# CameraCageBB.net
KiCad netlist of a schematic drawn in Altium Designer
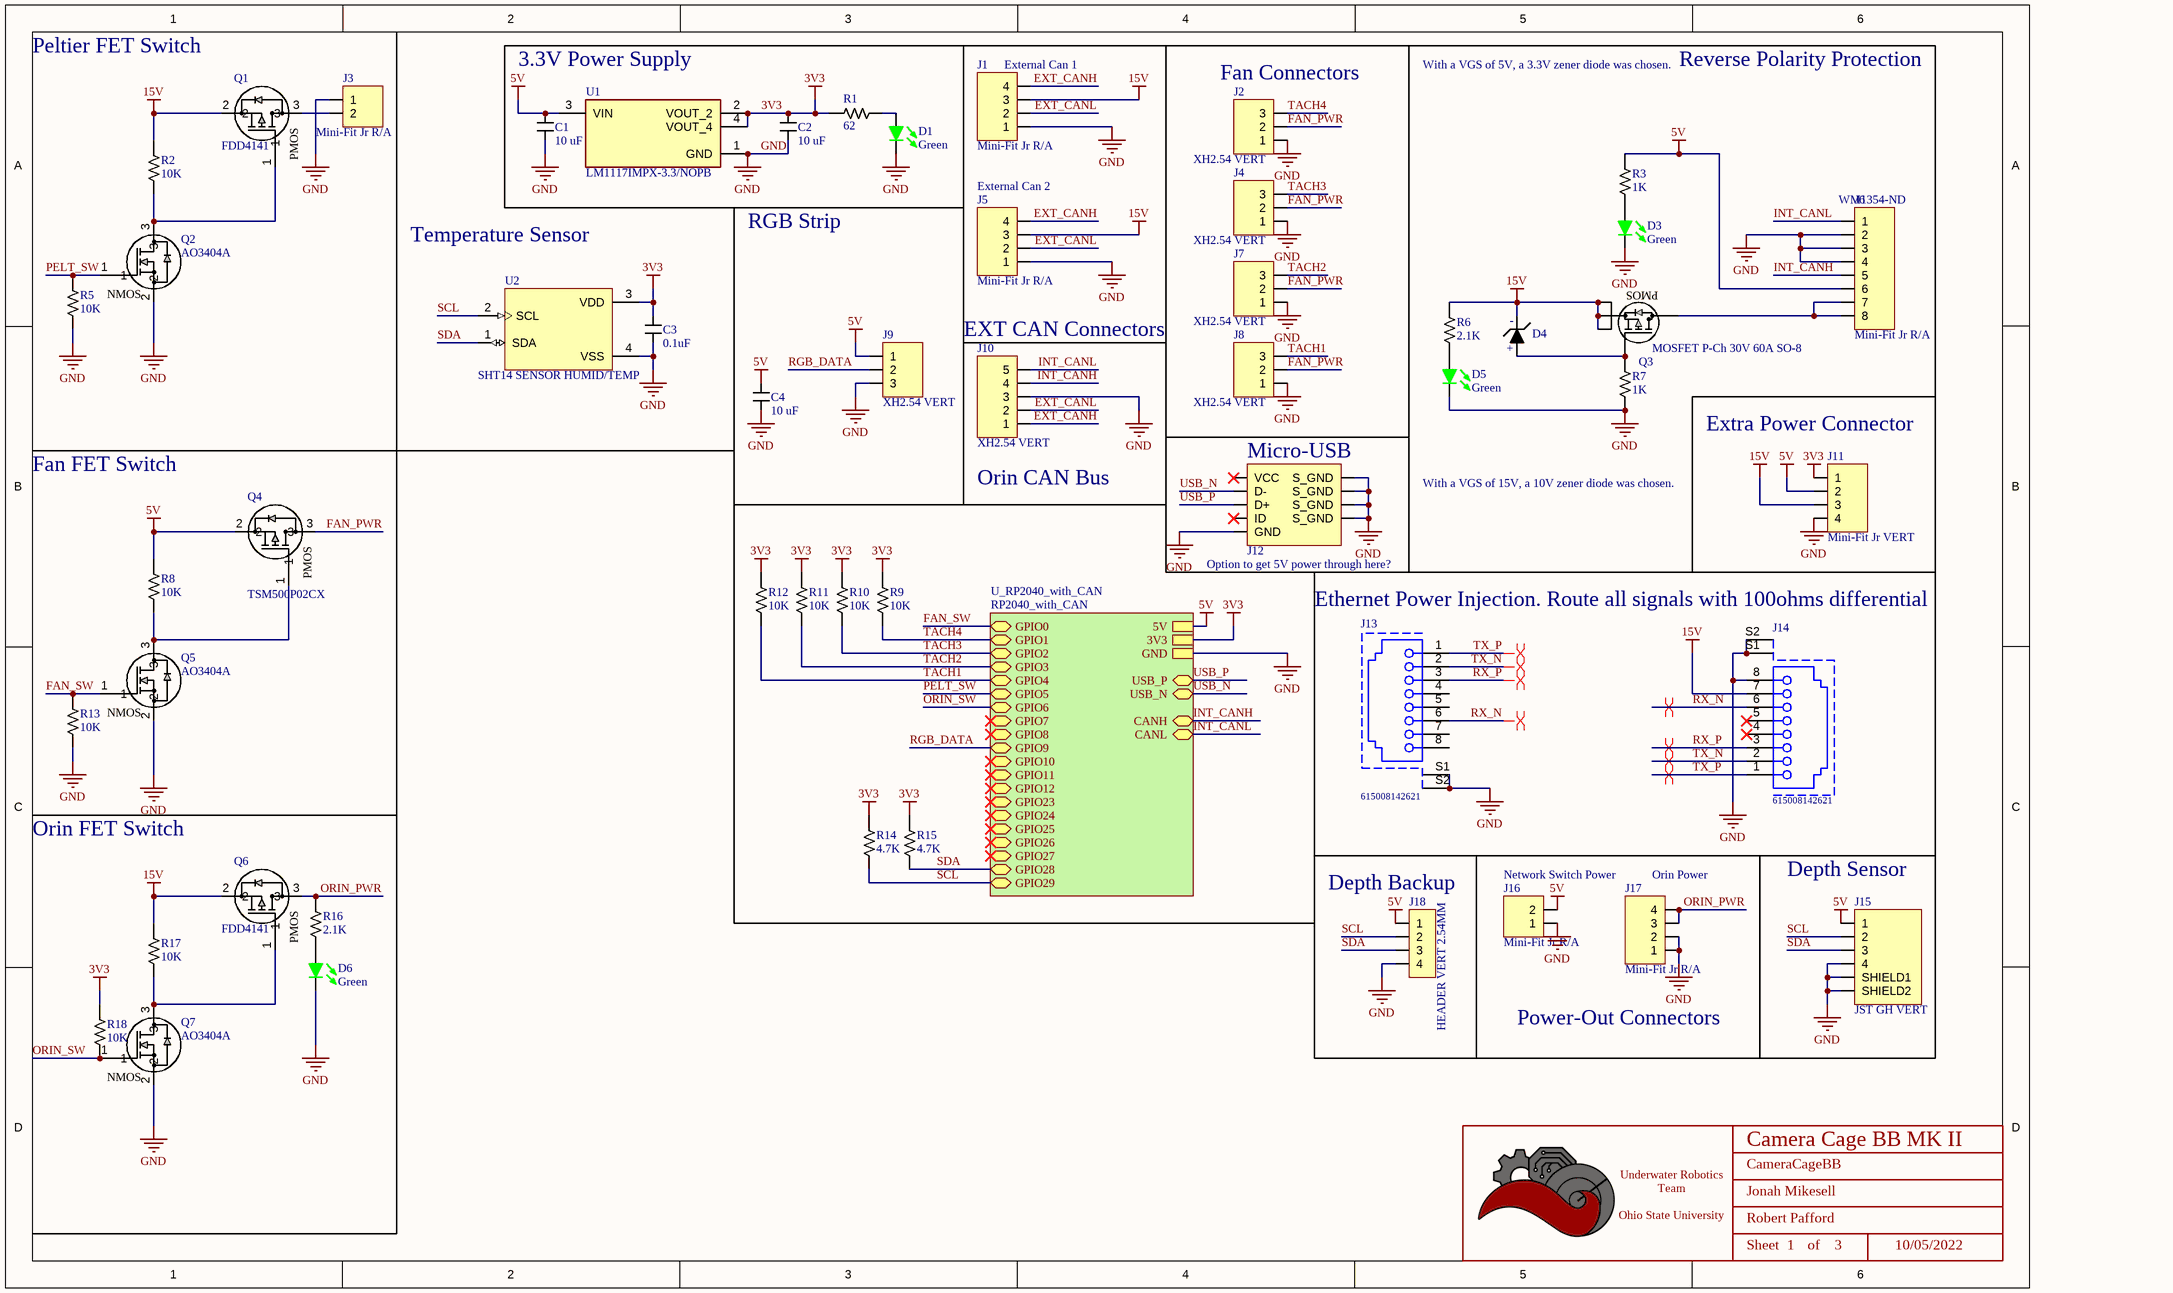
[diagram p0: CameraCageBB.SchDoc]

(export (version "E")
  (design (tool "Eeschema 10.0.6"))
  (components
    (comp (ref "*")
      (value "Title_Block")
      (footprint "LOGO")
      (description "UWRT Schematic Title Block Template\r\n\r\nCreated June 2021, Dylan Trainor")
      (libsource (lib "UWRT") (part "Title_Block"))
    )
    (comp (ref "C1")
      (value "10uF Ceramic 6.3V")
      (footprint "CAPACITOR_0603")
      (description "Cap 10uF 6.3V +/-20%\r\nCeramic 0603")
      (fields
        (field (name "TOLERANCE") "+/- 20%")
        (field (name "VOLTAGE") "6.3V")
        (field (name "VALUE (UF)") "10 uF")
        (field (name "MADE BY") "Flip B")
      )
      (libsource (lib "Capacitors") (part "CAPACITOR_10uF_0603"))
    )
    (comp (ref "C2")
      (value "10uF Ceramic 6.3V")
      (footprint "CAPACITOR_0603")
      (description "Cap 10uF 6.3V +/-20%\r\nCeramic 0603")
      (fields
        (field (name "TOLERANCE") "+/- 20%")
        (field (name "VOLTAGE") "6.3V")
        (field (name "VALUE (UF)") "10 uF")
        (field (name "MADE BY") "Flip B")
      )
      (libsource (lib "Capacitors") (part "CAPACITOR_10uF_0603"))
    )
    (comp (ref "C3")
      (value "0.1uF")
      (footprint "CAPACITOR_0603")
      (description "Cap 100nF 6.3V +/-10%\r\nCeramic 0603")
      (fields
        (field (name "TOLERANCE") "+/- 10%")
        (field (name "VOLTAGE") "6.3V")
        (field (name "MADE BY") "Flip B")
      )
      (libsource (lib "Capacitors") (part "CAPACITOR_0.1uF_0603"))
    )
    (comp (ref "C4")
      (value "10uF Ceramic 6.3V")
      (footprint "CAPACITOR_0603")
      (description "Cap 10uF 6.3V +/-20%\r\nCeramic 0603")
      (fields
        (field (name "TOLERANCE") "+/- 20%")
        (field (name "VOLTAGE") "6.3V")
        (field (name "VALUE (UF)") "10 uF")
        (field (name "MADE BY") "Flip B")
      )
      (libsource (lib "Capacitors") (part "CAPACITOR_10uF_0603"))
    )
    (comp (ref "D1")
      (value "IN-S63AT5G")
      (footprint "LED_0603")
      (description "LED Green Vf= 3V If = 0.005A\r\nIN-S63AT5G")
      (fields (field (name "COLOR") "Green") (field (name "MADE BY") "Robert Pafford"))
      (libsource (lib "Diodes") (part "LED_Green_0603_3V"))
    )
    (comp (ref "D3")
      (value "IN-S63AT5G")
      (footprint "LED_0603")
      (description "LED Green Vf= 3V If = 0.005A\r\nIN-S63AT5G")
      (fields (field (name "COLOR") "Green") (field (name "MADE BY") "Robert Pafford"))
      (libsource (lib "Diodes") (part "LED_Green_0603_3V"))
    )
    (comp (ref "D4")
      (value "Zener_Diode_10V_410mW")
      (footprint "SOD-123")
      (description "Zener Diode ¦ 10 V ¦ 410 mW ¦ SOD 123")
      (fields (field (name "POWER") "410mW") (field (name "MADE BY") "Nathan A"))
      (libsource (lib "Diodes") (part "Zener_Diode_10V_410mW"))
    )
    (comp (ref "D5")
      (value "IN-S63AT5G")
      (footprint "LED_0603")
      (description "LED Green Vf= 3V If = 0.005A\r\nIN-S63AT5G")
      (fields (field (name "COLOR") "Green") (field (name "MADE BY") "Robert Pafford"))
      (libsource (lib "Diodes") (part "LED_Green_0603_3V"))
    )
    (comp (ref "D6")
      (value "IN-S63AT5G")
      (footprint "LED_0603")
      (description "LED Green Vf= 3V If = 0.005A\r\nIN-S63AT5G")
      (fields (field (name "COLOR") "Green") (field (name "MADE BY") "Robert Pafford"))
      (libsource (lib "Diodes") (part "LED_Green_0603_3V"))
    )
    (comp (ref "J1")
      (value "Mini-Fit Jr R/A")
      (footprint "CONN_MOLEX_MINIFIT JR_4 POS_R/A")
      (description "Molex Minifit Jr. 5569 \r\n4 Pos R/A Natural")
      (fields (field (name "MANUFACTURER") "Molex") (field (name "CREATED BY") "Flip B"))
      (libsource (lib "Connectors") (part "CONN_MOLEX_MINIFIT JR_4POS_R/A"))
    )
    (comp (ref "J2")
      (value "XH2.54 VERT")
      (footprint "CONN_JST_XH254_3POS_VERT")
      (description "JST XH 2.54mm Pitch 3 Pos Vertical")
      (fields (field (name "MANUFACTURER") "JST") (field (name "CREATED BY") "Robert P"))
      (libsource (lib "") (part "CONN_JST_XH254_3POS_VERT_1"))
    )
    (comp (ref "J3")
      (value "Mini-Fit Jr R/A")
      (footprint "CONN_MOLEX_MINIFIT JR_2 POS_R/A")
      (description "Molex Minifit Jr. 5569 \r\n2 Pos R/A Natural")
      (fields (field (name "MANUFACTURER") "Molex") (field (name "CREATED BY") "Robert P"))
      (libsource (lib "") (part "CONN_MOLEX_MINIFIT JR_2POS_R/A_1"))
    )
    (comp (ref "J4")
      (value "XH2.54 VERT")
      (footprint "CONN_JST_XH254_3POS_VERT")
      (description "JST XH 2.54mm Pitch 3 Pos Vertical")
      (fields (field (name "MANUFACTURER") "JST") (field (name "CREATED BY") "Robert P"))
      (libsource (lib "") (part "CONN_JST_XH254_3POS_VERT_1"))
    )
    (comp (ref "J5")
      (value "Mini-Fit Jr R/A")
      (footprint "CONN_MOLEX_MINIFIT JR_4 POS_R/A")
      (description "Molex Minifit Jr. 5569 \r\n4 Pos R/A Natural")
      (fields (field (name "MANUFACTURER") "Molex") (field (name "CREATED BY") "Flip B"))
      (libsource (lib "Connectors") (part "CONN_MOLEX_MINIFIT JR_4POS_R/A"))
    )
    (comp (ref "J6")
      (value "Mini-Fit Jr R/A")
      (footprint "CONN_MOLEX_MINIFIT JR_8 POS_R/A")
      (description "Molex Minifit Jr. 5569 \r\n8 Pos R/A Natural")
      (fields
        (field (name "MANUFACTURER") "Molex")
        (field (name "SUPPLIER PART NUMBER 1") "WM1354-ND")
        (field (name "CREATED BY") "Flip B")
      )
      (libsource (lib "Connectors") (part "CONN_MOLEX_MINIFIT JR_8POS_R/A"))
    )
    (comp (ref "J7")
      (value "XH2.54 VERT")
      (footprint "CONN_JST_XH254_3POS_VERT")
      (description "JST XH 2.54mm Pitch 3 Pos Vertical")
      (fields (field (name "MANUFACTURER") "JST") (field (name "CREATED BY") "Robert P"))
      (libsource (lib "") (part "CONN_JST_XH254_3POS_VERT_1"))
    )
    (comp (ref "J8")
      (value "XH2.54 VERT")
      (footprint "CONN_JST_XH254_3POS_VERT")
      (description "JST XH 2.54mm Pitch 3 Pos Vertical")
      (fields (field (name "MANUFACTURER") "JST") (field (name "CREATED BY") "Robert P"))
      (libsource (lib "") (part "CONN_JST_XH254_3POS_VERT_1"))
    )
    (comp (ref "J9")
      (value "XH2.54 VERT")
      (footprint "CONN_JST_XH254_3POS_VERT")
      (description "JST XH 2.54mm Pitch 3 Pos Vertical")
      (fields (field (name "MANUFACTURER") "JST") (field (name "CREATED BY") "Robert P"))
      (libsource (lib "Connectors") (part "CONN_JST_XH254_3POS_VERT"))
    )
    (comp (ref "J10")
      (value "XH2.54 VERT")
      (footprint "CONN_JST_XH254_5POS_VERT")
      (description "JST XH 2.54mm Pitch 5 Pos Vertical")
      (fields (field (name "MANUFACTURER") "JST") (field (name "CREATED BY") "Robert P"))
      (libsource (lib "Connectors") (part "CONN_JST_XH254_5POS_VERT"))
    )
    (comp (ref "J11")
      (value "Mini-Fit Jr VERT")
      (footprint "CONN_MOLEX_MINIFIT JR_4 POS_VERT")
      (description "Molex Minifit Jr. 5566 \r\n4 Pos Vertical Natural")
      (fields (field (name "MANUFACTURER") "Molex") (field (name "CREATED BY") "Robert P"))
      (libsource (lib "Connectors") (part "CONN_MOLEX_MINIFIT JR_4POS_VERT"))
    )
    (comp (ref "J12")
      (value "USB_MICRO R/A")
      (footprint "CONN_MINIUSB")
      (description "Amphenol Micro USB-B\r\nUSB2.0 5 Pin Right Angle SMD")
      (fields (field (name "MANUFACTURER") "Amphenol") (field (name "CREATED BY") "Flip B"))
      (libsource (lib "Connectors") (part "CONN_MICROUSB"))
    )
    (comp (ref "J13")
      (value "615008142621")
      (footprint "615008142621")
      (fields (field (name "MANUFACTURER") "Wurth Elektronik") (field (name "PUBLISHER") "WurthElektronik"))
      (libsource (lib "Altium Content Vault") (part "WE-CN-1P-2F-J8"))
    )
    (comp (ref "J14")
      (value "615008142621")
      (footprint "615008142621")
      (fields (field (name "MANUFACTURER") "Wurth Elektronik") (field (name "PUBLISHER") "WurthElektronik"))
      (libsource (lib "Altium Content Vault") (part "WE-CN-1P-2F-J8"))
    )
    (comp (ref "J15")
      (value "JST GH VERT")
      (footprint "CONN_JST_BM04B-GHS-TBT(LF)(SN)(N)")
      (description "JST GH Pitch 4 Pos Vertical")
      (fields (field (name "MANUFACTURER") "JST") (field (name "CREATED BY") "Robert P"))
      (libsource (lib "Connectors") (part "CONN_JST_GH_4POS_VERT"))
    )
    (comp (ref "J16")
      (value "Mini-Fit Jr R/A")
      (footprint "CONN_MOLEX_MINIFIT JR_2 POS_R/A")
      (description "Molex Minifit Jr. 5569 \r\n2 Pos R/A Natural")
      (fields (field (name "MANUFACTURER") "Molex") (field (name "CREATED BY") "Robert P"))
      (libsource (lib "Connectors") (part "CONN_MOLEX_MINIFIT JR_2POS_R/A"))
    )
    (comp (ref "J17")
      (value "Mini-Fit Jr R/A")
      (footprint "CONN_MOLEX_MINIFIT JR_4 POS_R/A")
      (description "Molex Minifit Jr. 5569 \r\n4 Pos R/A Natural")
      (fields (field (name "MANUFACTURER") "Molex") (field (name "CREATED BY") "Flip B"))
      (libsource (lib "Connectors") (part "CONN_MOLEX_MINIFIT JR_4POS_R/A"))
    )
    (comp (ref "J18")
      (value "HEADER VERT 2.54MM")
      (footprint "HEADER_4PIN_2.54MM")
      (description "CONN HEADER VERT 4POS 2.54MM")
      (fields (field (name "MADE BY") "Robert Pafford"))
      (libsource (lib "Connectors") (part "HEADER_4PIN_2.54MM"))
    )
    (comp (ref "Q1")
      (value "FDD4141")
      (footprint "DPAK_ONS")
      (description "P-Channel 10.8A (Ta), 50A (Tc) 2.4W (Ta), 69W (Tc) Surface Mount D-PAK (TO-252AA)")
      (fields (field (name "CREATED BY") "Dylan T"))
      (libsource (lib "Transistors") (part "FDD4141"))
    )
    (comp (ref "Q2")
      (value "AO3404A")
      (footprint "SOT-23-3")
      (description "N-Channel 30 V 5.8A (Ta) 1.4W (Ta) Surface Mount SOT-23-3")
      (fields (field (name "CREATED BY") "Dylan T"))
      (libsource (lib "Transistors") (part "AO3404A"))
    )
    (comp (ref "Q3")
      (value "MOSFET P-Ch 30V 60A SO-8")
      (footprint "MOSFET_7DP-T1-GE3_VIS")
      (description "P-Channel 30 V 60A (Tc) 65.8W (Tc) Surface Mount PowerPAK® SO-8")
      (fields
        (field (name "MANUFACTURER_PART_NUMBER") "SIR167DP-T1-GE3")
        (field (name "COPYRIGHT") "Copyright (C) 2022 Ultra Librarian. All rights reserved.")
      )
      (libsource (lib "Transistors") (part "SIR167DP-T1-GE3"))
    )
    (comp (ref "Q4")
      (value "TSM500P02CX")
      (footprint "SOT-23-3")
      (description "P-Channel 20 V 4.7A (Tc) 1.56W (Tc) Surface Mount SOT-23")
      (fields (field (name "CREATED BY") "Robert Pafford"))
      (libsource (lib "Transistors") (part "TSM500P02CX"))
    )
    (comp (ref "Q5")
      (value "AO3404A")
      (footprint "SOT-23-3")
      (description "N-Channel 30 V 5.8A (Ta) 1.4W (Ta) Surface Mount SOT-23-3")
      (fields (field (name "CREATED BY") "Dylan T"))
      (libsource (lib "Transistors") (part "AO3404A"))
    )
    (comp (ref "Q6")
      (value "FDD4141")
      (footprint "DPAK_ONS")
      (description "P-Channel 10.8A (Ta), 50A (Tc) 2.4W (Ta), 69W (Tc) Surface Mount D-PAK (TO-252AA)")
      (fields (field (name "CREATED BY") "Dylan T"))
      (libsource (lib "Transistors") (part "FDD4141"))
    )
    (comp (ref "Q7")
      (value "AO3404A")
      (footprint "SOT-23-3")
      (description "N-Channel 30 V 5.8A (Ta) 1.4W (Ta) Surface Mount SOT-23-3")
      (fields (field (name "CREATED BY") "Dylan T"))
      (libsource (lib "Transistors") (part "AO3404A"))
    )
    (comp (ref "R1")
      (value "62 Ohm 1% 1/4W")
      (footprint "RESISTOR_0603")
      (description "RES SMD 62 OHM 1% 1/4W 0603")
      (fields
        (field (name "TOLERANCE") "+/- 1%")
        (field (name "VALUE  (OHMS)") "62")
        (field (name "MADE BY") "Robert Pafford")
      )
      (libsource (lib "Resistors") (part "RESISTOR_62_0603"))
    )
    (comp (ref "R2")
      (value "10k Ohm 5% 1/10W")
      (footprint "RESISTOR_0603")
      (description "RES 10k OHM 5% 1/10W 0603")
      (fields
        (field (name "TOLERANCE") "+/- 5%")
        (field (name "VALUE  (OHMS)") "10K")
        (field (name "MADE BY") "Robert Pafford")
      )
      (libsource (lib "Resistors") (part "RESISTOR_10K_0603"))
    )
    (comp (ref "R3")
      (value "1k Ohm 5% 1/8W")
      (footprint "RESISTOR_0603")
      (description "RES 1k OHM 5% 1/8W 0603")
      (fields
        (field (name "TOLERANCE") "+/- 5%")
        (field (name "VALUE  (OHMS)") "1K")
        (field (name "MADE BY") "Robert Pafford")
      )
      (libsource (lib "Resistors") (part "RESISTOR_1K_0603"))
    )
    (comp (ref "R5")
      (value "10k Ohm 5% 1/10W")
      (footprint "RESISTOR_0603")
      (description "RES 10k OHM 5% 1/10W 0603")
      (fields
        (field (name "TOLERANCE") "+/- 5%")
        (field (name "VALUE  (OHMS)") "10K")
        (field (name "MADE BY") "Robert Pafford")
      )
      (libsource (lib "Resistors") (part "RESISTOR_10K_0603"))
    )
    (comp (ref "R6")
      (value "2.1k Ohm 5% 1/8W")
      (footprint "RESISTOR_0603")
      (description "RES 2.1k OHM 5% 1/8W 0603")
      (fields
        (field (name "TOLERANCE") "+/- 5%")
        (field (name "VALUE  (OHMS)") "2.1K")
        (field (name "MADE BY") "Robert Pafford")
      )
      (libsource (lib "Resistors") (part "RESISTOR_2.1K_0603"))
    )
    (comp (ref "R7")
      (value "1k Ohm 5% 1/8W")
      (footprint "RESISTOR_0603")
      (description "RES 1k OHM 5% 1/8W 0603")
      (fields
        (field (name "TOLERANCE") "+/- 5%")
        (field (name "VALUE  (OHMS)") "1K")
        (field (name "MADE BY") "Robert Pafford")
      )
      (libsource (lib "Resistors") (part "RESISTOR_1K_0603"))
    )
    (comp (ref "R8")
      (value "10k Ohm 5% 1/10W")
      (footprint "RESISTOR_0603")
      (description "RES 10k OHM 5% 1/10W 0603")
      (fields
        (field (name "TOLERANCE") "+/- 5%")
        (field (name "VALUE  (OHMS)") "10K")
        (field (name "MADE BY") "Robert Pafford")
      )
      (libsource (lib "Resistors") (part "RESISTOR_10K_0603"))
    )
    (comp (ref "R9")
      (value "10k Ohm 5% 1/10W")
      (footprint "RESISTOR_0603")
      (description "RES 10k OHM 5% 1/10W 0603")
      (fields
        (field (name "TOLERANCE") "+/- 5%")
        (field (name "VALUE  (OHMS)") "10K")
        (field (name "MADE BY") "Robert Pafford")
      )
      (libsource (lib "Resistors") (part "RESISTOR_10K_0603"))
    )
    (comp (ref "R10")
      (value "10k Ohm 5% 1/10W")
      (footprint "RESISTOR_0603")
      (description "RES 10k OHM 5% 1/10W 0603")
      (fields
        (field (name "TOLERANCE") "+/- 5%")
        (field (name "VALUE  (OHMS)") "10K")
        (field (name "MADE BY") "Robert Pafford")
      )
      (libsource (lib "Resistors") (part "RESISTOR_10K_0603"))
    )
    (comp (ref "R11")
      (value "10k Ohm 5% 1/10W")
      (footprint "RESISTOR_0603")
      (description "RES 10k OHM 5% 1/10W 0603")
      (fields
        (field (name "TOLERANCE") "+/- 5%")
        (field (name "VALUE  (OHMS)") "10K")
        (field (name "MADE BY") "Robert Pafford")
      )
      (libsource (lib "Resistors") (part "RESISTOR_10K_0603"))
    )
    (comp (ref "R12")
      (value "10k Ohm 5% 1/10W")
      (footprint "RESISTOR_0603")
      (description "RES 10k OHM 5% 1/10W 0603")
      (fields
        (field (name "TOLERANCE") "+/- 5%")
        (field (name "VALUE  (OHMS)") "10K")
        (field (name "MADE BY") "Robert Pafford")
      )
      (libsource (lib "Resistors") (part "RESISTOR_10K_0603"))
    )
    (comp (ref "R13")
      (value "10k Ohm 5% 1/10W")
      (footprint "RESISTOR_0603")
      (description "RES 10k OHM 5% 1/10W 0603")
      (fields
        (field (name "TOLERANCE") "+/- 5%")
        (field (name "VALUE  (OHMS)") "10K")
        (field (name "MADE BY") "Robert Pafford")
      )
      (libsource (lib "Resistors") (part "RESISTOR_10K_0603"))
    )
    (comp (ref "R14")
      (value "4.7k Ohm 5% 1/10W")
      (footprint "RESISTOR_0603")
      (description "RES 4.7k OHM 5% 1/10W 0603")
      (fields
        (field (name "TOLERANCE") "+/- 5%")
        (field (name "VALUE  (OHMS)") "4.7K")
        (field (name "MADE BY") "Robert Pafford")
      )
      (libsource (lib "Resistors") (part "RESISTOR_4.7K_0603"))
    )
    (comp (ref "R15")
      (value "4.7k Ohm 5% 1/10W")
      (footprint "RESISTOR_0603")
      (description "RES 4.7k OHM 5% 1/10W 0603")
      (fields
        (field (name "TOLERANCE") "+/- 5%")
        (field (name "VALUE  (OHMS)") "4.7K")
        (field (name "MADE BY") "Robert Pafford")
      )
      (libsource (lib "Resistors") (part "RESISTOR_4.7K_0603"))
    )
    (comp (ref "R16")
      (value "2.1k Ohm 5% 1/8W")
      (footprint "RESISTOR_0603")
      (description "RES 2.1k OHM 5% 1/8W 0603")
      (fields
        (field (name "TOLERANCE") "+/- 5%")
        (field (name "VALUE  (OHMS)") "2.1K")
        (field (name "MADE BY") "Robert Pafford")
      )
      (libsource (lib "Resistors") (part "RESISTOR_2.1K_0603"))
    )
    (comp (ref "R17")
      (value "10k Ohm 5% 1/10W")
      (footprint "RESISTOR_0603")
      (description "RES 10k OHM 5% 1/10W 0603")
      (fields
        (field (name "TOLERANCE") "+/- 5%")
        (field (name "VALUE  (OHMS)") "10K")
        (field (name "MADE BY") "Robert Pafford")
      )
      (libsource (lib "Resistors") (part "RESISTOR_10K_0603"))
    )
    (comp (ref "R18")
      (value "10k Ohm 5% 1/10W")
      (footprint "RESISTOR_0603")
      (description "RES 10k OHM 5% 1/10W 0603")
      (fields
        (field (name "TOLERANCE") "+/- 5%")
        (field (name "VALUE  (OHMS)") "10K")
        (field (name "MADE BY") "Robert Pafford")
      )
      (libsource (lib "Resistors") (part "RESISTOR_10K_0603"))
    )
    (comp (ref "U1")
      (value "LM1117IMPX-3.3/NOPB")
      (footprint "SOT-223-4")
      (description "800-mA 15-V linear voltage regulator 4-SOT-223 -40 to 125")
      (fields (field (name "MF") "Texas Instruments"))
      (libsource (lib "Integrated Circuits") (part "LM1117IMPX-3.3/NOPB"))
    )
    (comp (ref "U2")
      (value "SHT14 SENSOR HUMID/TEMP")
      (footprint "XDCR_SHT41-AD1B-R2")
      (description "Digital Relative Humidity Temperature Sensor, Â±1.8 / max 2.5 %RH, Â±0.2 Â°C, Ultra-Low-Power")
      (fields (field (name "MP") "SHT41-AD1B-R2") (field (name "MF") "Sensirion"))
      (libsource (lib "Integrated Circuits") (part "SHT41-AD1B-R2"))
    )
  )
  (nets
    (net (code "1") (name "/EXT_CANH") (class "Default")
      (node (ref "J1") (pin "4") (pinfunction "4_4") (pintype "passive"))
      (node (ref "J10") (pin "1") (pinfunction "1_1") (pintype "passive"))
      (node (ref "J5") (pin "4") (pinfunction "4_4") (pintype "passive"))
    )
    (net (code "2") (name "/EXT_CANL") (class "Default")
      (node (ref "J1") (pin "2") (pinfunction "2_2") (pintype "passive"))
      (node (ref "J10") (pin "2") (pinfunction "2_2") (pintype "passive"))
      (node (ref "J5") (pin "2") (pinfunction "2_2") (pintype "passive"))
    )
    (net (code "3") (name "/FAN_PWR") (class "Default")
      (node (ref "J2") (pin "2") (pinfunction "2_2") (pintype "passive"))
      (node (ref "J4") (pin "2") (pinfunction "2_2") (pintype "passive"))
      (node (ref "J7") (pin "2") (pinfunction "2_2") (pintype "passive"))
      (node (ref "J8") (pin "2") (pinfunction "2_2") (pintype "passive"))
      (node (ref "Q4") (pin "3") (pinfunction "3_3") (pintype "passive"))
    )
    (net (code "4") (name "/FAN_SW") (class "Default")
      (node (ref "Q5") (pin "1") (pinfunction "1_1") (pintype "passive"))
      (node (ref "R13") (pin "1") (pinfunction "1_1") (pintype "passive"))
    )
    (net (code "15") (name "/INT_CANH") (class "Default")
      (node (ref "J10") (pin "4") (pinfunction "4_4") (pintype "passive"))
      (node (ref "J6") (pin "5") (pinfunction "5_5") (pintype "passive"))
    )
    (net (code "16") (name "/INT_CANL") (class "Default")
      (node (ref "J10") (pin "5") (pinfunction "5_5") (pintype "passive"))
      (node (ref "J6") (pin "1") (pinfunction "1_1") (pintype "passive"))
    )
    (net (code "17") (name "/ORIN_PWR") (class "Default")
      (node (ref "J17") (pin "3") (pinfunction "3_3") (pintype "passive"))
      (node (ref "J17") (pin "4") (pinfunction "4_4") (pintype "passive"))
      (node (ref "Q6") (pin "3") (pinfunction "3_3") (pintype "passive"))
      (node (ref "R16") (pin "1") (pinfunction "1_1") (pintype "passive"))
    )
    (net (code "18") (name "/ORIN_SW") (class "Default")
      (node (ref "Q7") (pin "1") (pinfunction "1_1") (pintype "passive"))
      (node (ref "R18") (pin "2") (pinfunction "2_2") (pintype "passive"))
    )
    (net (code "19") (name "/PELT_SW") (class "Default")
      (node (ref "Q2") (pin "1") (pinfunction "1_1") (pintype "passive"))
      (node (ref "R5") (pin "1") (pinfunction "1_1") (pintype "passive"))
    )
    (net (code "20") (name "/RGB_DATA") (class "Default")
      (node (ref "J9") (pin "2") (pinfunction "2_2") (pintype "passive"))
    )
    (net (code "21") (name "/RX_N") (class "Default")
      (node (ref "J13") (pin "6") (pinfunction "6_6") (pintype "passive"))
      (node (ref "J14") (pin "6") (pinfunction "6_6") (pintype "passive"))
    )
    (net (code "22") (name "/RX_P") (class "Default")
      (node (ref "J13") (pin "3") (pinfunction "3_3") (pintype "passive"))
      (node (ref "J14") (pin "3") (pinfunction "3_3") (pintype "passive"))
    )
    (net (code "23") (name "/SCL") (class "Default")
      (node (ref "J15") (pin "2") (pinfunction "2_2") (pintype "passive"))
      (node (ref "J18") (pin "2") (pinfunction "2_2") (pintype "passive"))
      (node (ref "R14") (pin "2") (pinfunction "2_2") (pintype "passive"))
      (node (ref "U2") (pin "2") (pinfunction "SCL_2") (pintype "input"))
    )
    (net (code "24") (name "/SDA") (class "Default")
      (node (ref "J15") (pin "3") (pinfunction "3_3") (pintype "passive"))
      (node (ref "J18") (pin "3") (pinfunction "3_3") (pintype "passive"))
      (node (ref "R15") (pin "2") (pinfunction "2_2") (pintype "passive"))
      (node (ref "U2") (pin "1") (pinfunction "SDA_1") (pintype "bidirectional"))
    )
    (net (code "25") (name "/TACH1") (class "Default")
      (node (ref "J8") (pin "3") (pinfunction "3_3") (pintype "passive"))
      (node (ref "R12") (pin "2") (pinfunction "2_2") (pintype "passive"))
    )
    (net (code "26") (name "/TACH2") (class "Default")
      (node (ref "J7") (pin "3") (pinfunction "3_3") (pintype "passive"))
      (node (ref "R11") (pin "2") (pinfunction "2_2") (pintype "passive"))
    )
    (net (code "27") (name "/TACH3") (class "Default")
      (node (ref "J4") (pin "3") (pinfunction "3_3") (pintype "passive"))
      (node (ref "R10") (pin "2") (pinfunction "2_2") (pintype "passive"))
    )
    (net (code "28") (name "/TACH4") (class "Default")
      (node (ref "J2") (pin "3") (pinfunction "3_3") (pintype "passive"))
      (node (ref "R9") (pin "2") (pinfunction "2_2") (pintype "passive"))
    )
    (net (code "29") (name "/TX_N") (class "Default")
      (node (ref "J13") (pin "2") (pinfunction "2_2") (pintype "passive"))
      (node (ref "J14") (pin "2") (pinfunction "2_2") (pintype "passive"))
    )
    (net (code "30") (name "/TX_P") (class "Default")
      (node (ref "J13") (pin "1") (pinfunction "1_1") (pintype "passive"))
      (node (ref "J14") (pin "1") (pinfunction "1_1") (pintype "passive"))
    )
    (net (code "31") (name "/USB_N") (class "Default")
      (node (ref "J12") (pin "2") (pinfunction "D-_2") (pintype "passive"))
    )
    (net (code "32") (name "/USB_P") (class "Default")
      (node (ref "J12") (pin "3") (pinfunction "D+_3") (pintype "passive"))
    )
    (net (code "33") (name "3V3") (class "Default")
      (node (ref "C2") (pin "1") (pinfunction "1_1") (pintype "passive"))
      (node (ref "C3") (pin "1") (pinfunction "1_1") (pintype "passive"))
      (node (ref "J11") (pin "1") (pinfunction "1_1") (pintype "passive"))
      (node (ref "R1") (pin "1") (pinfunction "1_1") (pintype "passive"))
      (node (ref "R10") (pin "1") (pinfunction "1_1") (pintype "passive"))
      (node (ref "R11") (pin "1") (pinfunction "1_1") (pintype "passive"))
      (node (ref "R12") (pin "1") (pinfunction "1_1") (pintype "passive"))
      (node (ref "R14") (pin "1") (pinfunction "1_1") (pintype "passive"))
      (node (ref "R15") (pin "1") (pinfunction "1_1") (pintype "passive"))
      (node (ref "R18") (pin "1") (pinfunction "1_1") (pintype "passive"))
      (node (ref "R9") (pin "1") (pinfunction "1_1") (pintype "passive"))
      (node (ref "U1") (pin "2") (pinfunction "VOUT_2_2") (pintype "power_in"))
      (node (ref "U1") (pin "4") (pinfunction "VOUT_4_4") (pintype "power_in"))
      (node (ref "U2") (pin "3") (pinfunction "VDD_3") (pintype "power_in"))
    )
    (net (code "34") (name "5V") (class "Default")
      (node (ref "C1") (pin "1") (pinfunction "1_1") (pintype "passive"))
      (node (ref "C4") (pin "1") (pinfunction "1_1") (pintype "passive"))
      (node (ref "J11") (pin "2") (pinfunction "2_2") (pintype "passive"))
      (node (ref "J15") (pin "1") (pinfunction "1_1") (pintype "passive"))
      (node (ref "J16") (pin "2") (pinfunction "2_2") (pintype "passive"))
      (node (ref "J18") (pin "1") (pinfunction "1_1") (pintype "passive"))
      (node (ref "J6") (pin "6") (pinfunction "6_6") (pintype "passive"))
      (node (ref "J9") (pin "1") (pinfunction "1_1") (pintype "passive"))
      (node (ref "Q4") (pin "2") (pinfunction "2_2") (pintype "passive"))
      (node (ref "R3") (pin "1") (pinfunction "1_1") (pintype "passive"))
      (node (ref "R8") (pin "1") (pinfunction "1_1") (pintype "passive"))
      (node (ref "U1") (pin "3") (pinfunction "VIN_3") (pintype "power_in"))
    )
    (net (code "35") (name "15V") (class "Default")
      (node (ref "D4") (pin "2") (pinfunction "2_2") (pintype "passive"))
      (node (ref "J1") (pin "3") (pinfunction "3_3") (pintype "passive"))
      (node (ref "J11") (pin "3") (pinfunction "3_3") (pintype "passive"))
      (node (ref "J14") (pin "7") (pinfunction "7_7") (pintype "passive"))
      (node (ref "J5") (pin "3") (pinfunction "3_3") (pintype "passive"))
      (node (ref "Q1") (pin "2") (pinfunction "2_2") (pintype "passive"))
      (node (ref "Q3") (pin "1") (pinfunction "S_1") (pintype "passive"))
      (node (ref "Q3") (pin "2") (pinfunction "S_2") (pintype "passive"))
      (node (ref "Q3") (pin "3") (pinfunction "S_3") (pintype "passive"))
      (node (ref "Q6") (pin "2") (pinfunction "2_2") (pintype "passive"))
      (node (ref "R17") (pin "1") (pinfunction "1_1") (pintype "passive"))
      (node (ref "R2") (pin "1") (pinfunction "1_1") (pintype "passive"))
      (node (ref "R6") (pin "1") (pinfunction "1_1") (pintype "passive"))
    )
    (net (code "36") (name "GND") (class "Default")
      (node (ref "C1") (pin "2") (pinfunction "2_2") (pintype "passive"))
      (node (ref "C2") (pin "2") (pinfunction "2_2") (pintype "passive"))
      (node (ref "C3") (pin "2") (pinfunction "2_2") (pintype "passive"))
      (node (ref "C4") (pin "2") (pinfunction "2_2") (pintype "passive"))
      (node (ref "D1") (pin "2") (pinfunction "2_2") (pintype "passive"))
      (node (ref "D3") (pin "2") (pinfunction "2_2") (pintype "passive"))
      (node (ref "D5") (pin "2") (pinfunction "2_2") (pintype "passive"))
      (node (ref "D6") (pin "2") (pinfunction "2_2") (pintype "passive"))
      (node (ref "J1") (pin "1") (pinfunction "1_1") (pintype "passive"))
      (node (ref "J10") (pin "3") (pinfunction "3_3") (pintype "passive"))
      (node (ref "J11") (pin "4") (pinfunction "4_4") (pintype "passive"))
      (node (ref "J12") (pin "5") (pinfunction "GND_5") (pintype "passive"))
      (node (ref "J12") (pin "6") (pinfunction "S_GND_6") (pintype "passive"))
      (node (ref "J12") (pin "7") (pinfunction "S_GND_7") (pintype "passive"))
      (node (ref "J12") (pin "8") (pinfunction "S_GND_8") (pintype "passive"))
      (node (ref "J12") (pin "9") (pinfunction "S_GND_9") (pintype "passive"))
      (node (ref "J13") (pin "S1") (pinfunction "S1_S1") (pintype "passive"))
      (node (ref "J13") (pin "S2") (pinfunction "S2_S2") (pintype "passive"))
      (node (ref "J14") (pin "8") (pinfunction "8_8") (pintype "passive"))
      (node (ref "J14") (pin "S1") (pinfunction "S1_S1") (pintype "passive"))
      (node (ref "J14") (pin "S2") (pinfunction "S2_S2") (pintype "passive"))
      (node (ref "J15") (pin "4") (pinfunction "4_4") (pintype "passive"))
      (node (ref "J15") (pin "S1") (pinfunction "SHIELD1_S1") (pintype "passive"))
      (node (ref "J15") (pin "S2") (pinfunction "SHIELD2_S2") (pintype "passive"))
      (node (ref "J16") (pin "1") (pinfunction "1_1") (pintype "passive"))
      (node (ref "J17") (pin "1") (pinfunction "1_1") (pintype "passive"))
      (node (ref "J17") (pin "2") (pinfunction "2_2") (pintype "passive"))
      (node (ref "J18") (pin "4") (pinfunction "4_4") (pintype "passive"))
      (node (ref "J2") (pin "1") (pinfunction "1_1") (pintype "passive"))
      (node (ref "J3") (pin "1") (pinfunction "1_1") (pintype "passive"))
      (node (ref "J4") (pin "1") (pinfunction "1_1") (pintype "passive"))
      (node (ref "J5") (pin "1") (pinfunction "1_1") (pintype "passive"))
      (node (ref "J6") (pin "2") (pinfunction "2_2") (pintype "passive"))
      (node (ref "J6") (pin "3") (pinfunction "3_3") (pintype "passive"))
      (node (ref "J6") (pin "4") (pinfunction "4_4") (pintype "passive"))
      (node (ref "J7") (pin "1") (pinfunction "1_1") (pintype "passive"))
      (node (ref "J8") (pin "1") (pinfunction "1_1") (pintype "passive"))
      (node (ref "J9") (pin "3") (pinfunction "3_3") (pintype "passive"))
      (node (ref "Q2") (pin "2") (pinfunction "2_2") (pintype "passive"))
      (node (ref "Q5") (pin "2") (pinfunction "2_2") (pintype "passive"))
      (node (ref "Q7") (pin "2") (pinfunction "2_2") (pintype "passive"))
      (node (ref "R13") (pin "2") (pinfunction "2_2") (pintype "passive"))
      (node (ref "R5") (pin "2") (pinfunction "2_2") (pintype "passive"))
      (node (ref "R7") (pin "2") (pinfunction "2_2") (pintype "passive"))
      (node (ref "U1") (pin "1") (pinfunction "GND_1") (pintype "power_in"))
      (node (ref "U2") (pin "4") (pinfunction "VSS_4") (pintype "power_in"))
    )
    (net (code "37") (name "Net-(D1-Pad1)") (class "Default")
      (node (ref "D1") (pin "1") (pinfunction "1_1") (pintype "passive"))
      (node (ref "R1") (pin "2") (pinfunction "2_2") (pintype "passive"))
    )
    (net (code "38") (name "Net-(D3-Pad1)") (class "Default")
      (node (ref "D3") (pin "1") (pinfunction "1_1") (pintype "passive"))
      (node (ref "R3") (pin "2") (pinfunction "2_2") (pintype "passive"))
    )
    (net (code "39") (name "Net-(D5-Pad1)") (class "Default")
      (node (ref "D5") (pin "1") (pinfunction "1_1") (pintype "passive"))
      (node (ref "R6") (pin "2") (pinfunction "2_2") (pintype "passive"))
    )
    (net (code "40") (name "Net-(D6-Pad1)") (class "Default")
      (node (ref "D6") (pin "1") (pinfunction "1_1") (pintype "passive"))
      (node (ref "R16") (pin "2") (pinfunction "2_2") (pintype "passive"))
    )
    (net (code "41") (name "Net-(J3-Pad2)") (class "Default")
      (node (ref "J3") (pin "2") (pinfunction "2_2") (pintype "passive"))
      (node (ref "Q1") (pin "3") (pinfunction "3_3") (pintype "passive"))
    )
    (net (code "42") (name "Net-(J6-Pad7)") (class "Default")
      (node (ref "J6") (pin "7") (pinfunction "7_7") (pintype "passive"))
      (node (ref "J6") (pin "8") (pinfunction "8_8") (pintype "passive"))
      (node (ref "Q3") (pin "D") (pinfunction "D_D") (pintype "passive"))
    )
    (net (code "43") (name "Net-(Q1-Pad1)") (class "Default")
      (node (ref "Q1") (pin "1") (pinfunction "1_1") (pintype "passive"))
      (node (ref "Q2") (pin "3") (pinfunction "3_3") (pintype "passive"))
      (node (ref "R2") (pin "2") (pinfunction "2_2") (pintype "passive"))
    )
    (net (code "44") (name "Net-(Q3-G)") (class "Default")
      (node (ref "D4") (pin "1") (pinfunction "1_1") (pintype "passive"))
      (node (ref "Q3") (pin "4") (pinfunction "G_4") (pintype "passive"))
      (node (ref "R7") (pin "1") (pinfunction "1_1") (pintype "passive"))
    )
    (net (code "45") (name "Net-(Q4-Pad1)") (class "Default")
      (node (ref "Q4") (pin "1") (pinfunction "1_1") (pintype "passive"))
      (node (ref "Q5") (pin "3") (pinfunction "3_3") (pintype "passive"))
      (node (ref "R8") (pin "2") (pinfunction "2_2") (pintype "passive"))
    )
    (net (code "46") (name "Net-(Q6-Pad1)") (class "Default")
      (node (ref "Q6") (pin "1") (pinfunction "1_1") (pintype "passive"))
      (node (ref "Q7") (pin "3") (pinfunction "3_3") (pintype "passive"))
      (node (ref "R17") (pin "2") (pinfunction "2_2") (pintype "passive"))
    )
    (net (code "47") (name "unconnected-(J12-ID-Pad4)") (class "Default")
      (node (ref "J12") (pin "4") (pinfunction "ID_4") (pintype "passive+no_connect"))
    )
    (net (code "48") (name "unconnected-(J12-VCC-Pad1)") (class "Default")
      (node (ref "J12") (pin "1") (pinfunction "VCC_1") (pintype "passive+no_connect"))
    )
    (net (code "49") (name "unconnected-(J13-Pad4)") (class "Default")
      (node (ref "J13") (pin "4") (pinfunction "4_4") (pintype "passive"))
    )
    (net (code "50") (name "unconnected-(J13-Pad5)") (class "Default")
      (node (ref "J13") (pin "5") (pinfunction "5_5") (pintype "passive"))
    )
    (net (code "51") (name "unconnected-(J13-Pad7)") (class "Default")
      (node (ref "J13") (pin "7") (pinfunction "7_7") (pintype "passive"))
    )
    (net (code "52") (name "unconnected-(J13-Pad8)") (class "Default")
      (node (ref "J13") (pin "8") (pinfunction "8_8") (pintype "passive"))
    )
    (net (code "53") (name "unconnected-(J14-Pad4)") (class "Default")
      (node (ref "J14") (pin "4") (pinfunction "4_4") (pintype "passive+no_connect"))
    )
    (net (code "54") (name "unconnected-(J14-Pad5)") (class "Default")
      (node (ref "J14") (pin "5") (pinfunction "5_5") (pintype "passive+no_connect"))
    )
  )
)
